# IonValveCtrl.net
KiCad netlist of a schematic drawn in Altium Designer
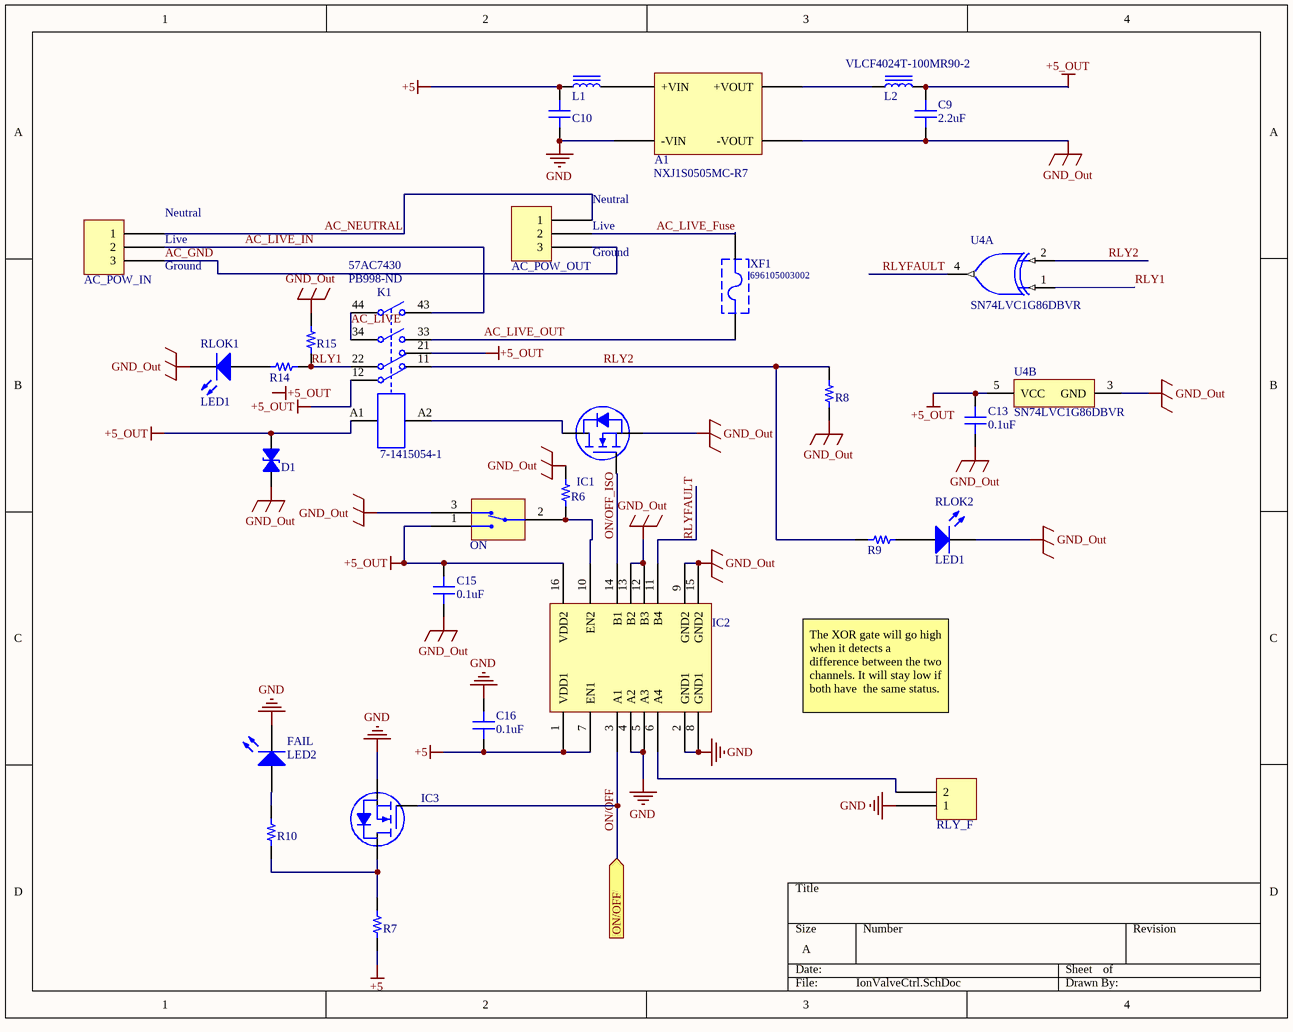
[diagram p0: IonValveCtrl.SchDoc]

(export (version "E")
  (design (tool "Eeschema 10.0.6"))
  (components
    (comp (ref "A1")
      (value "NXJ1S0505MC-R7")
      (footprint "MURATA NXJ1")
      (description "DC/DC SM 1W 5V-5V SINGLE 4.2KV")
      (fields (field (name "MANUFACTURER") "Murata Power Solutions Inc."))
      (libsource (lib "Celestial Library Database") (part "MURATA NXJ1"))
    )
    (comp (ref "AC_POW_IN")
      (value "691508110303")
      (footprint "WURTH 691508110303")
      (description "CONN TERM BLK 3POS 3.5MM BLACK")
      (fields (field (name "MANUFACTURER") "Wurth Electronics Inc") (field (name "VOLTAGE") "300V"))
      (libsource (lib "Celestial Library Database") (part "3 Pin"))
    )
    (comp (ref "AC_POW_OUT")
      (value "691508110303")
      (footprint "WURTH 691508110303")
      (description "CONN TERM BLK 3POS 3.5MM BLACK")
      (fields (field (name "MANUFACTURER") "Wurth Electronics Inc") (field (name "VOLTAGE") "300V"))
      (libsource (lib "Celestial Library Database") (part "3 Pin"))
    )
    (comp (ref "C9")
      (value "2.2uF")
      (footprint "CAP 1206/3216")
      (description "CAP CER 2.2UF 100V X7R 1206")
      (fields
        (field (name "PART NUMBER") "CL31B225KCHSNNE")
        (field (name "MANUFACTURER") "Samsung Electro-Mechanics America, Inc.")
      )
      (libsource (lib "Celestial Library Database") (part "Capacitor"))
    )
    (comp (ref "C10")
      (value "4.7uF")
      (footprint "CAP 1206/3216 - 1.8MM")
      (description "CAP CER 4.7UF 10V X7R 1206")
      (fields
        (field (name "PART NUMBER") "CL31B475KPHNNNE")
        (field (name "MANUFACTURER") "Samsung Electro-Mechanics America, Inc.")
      )
      (libsource (lib "Celestial Library Database") (part "Capacitor"))
    )
    (comp (ref "C13")
      (value "0.1uF")
      (footprint "CAP 0805/2012")
      (description "CAP CER 0.1UF 25V X7R 0805")
      (fields
        (field (name "PART NUMBER") "CL21B104KACNNNC")
        (field (name "MANUFACTURER") "Samsung Electro-Mechanics America, Inc.")
      )
      (libsource (lib "Celestial Library Database") (part "Capacitor"))
    )
    (comp (ref "C15")
      (value "0.1uF")
      (footprint "CAP 0805/2012")
      (description "CAP CER 0.1UF 25V X7R 0805")
      (fields
        (field (name "PART NUMBER") "CL21B104KACNNNC")
        (field (name "MANUFACTURER") "Samsung Electro-Mechanics America, Inc.")
      )
      (libsource (lib "Celestial Library Database") (part "Capacitor"))
    )
    (comp (ref "C16")
      (value "0.1uF")
      (footprint "CAP 0805/2012")
      (description "CAP CER 0.1UF 25V X7R 0805")
      (fields
        (field (name "PART NUMBER") "CL21B104KACNNNC")
        (field (name "MANUFACTURER") "Samsung Electro-Mechanics America, Inc.")
      )
      (libsource (lib "Celestial Library Database") (part "Capacitor"))
    )
    (comp (ref "D1")
      (value "SM15T15CA")
      (footprint "ST DO214AB SMC")
      (description "TVS DIODE 12.8VWM 27.2VC SMC")
      (fields (field (name "MANUFACTURER") "STMicroelectronics"))
      (libsource (lib "Celestial Library Database") (part "Diode Zener Bidirectional"))
    )
    (comp (ref "FAIL")
      (value "LED2")
      (footprint "LED-1")
      (description "Typical RED GaAs LED")
      (fields (field (name "PUBLISHER") "Altium Limited"))
      (libsource (lib "Miscellaneous Devices") (part "LED1"))
    )
    (comp (ref "IC1")
      (value "BSS138WH6327XTSA1")
      (footprint "INFINEON SOT-323-3")
      (description "MOSFET N-CH 60V 280MA SOT-323")
      (fields (field (name "MANUFACTURER") "Infineon Technologies"))
      (libsource (lib "Celestial Library Database") (part "INFINEON MOSFET N-CH SOT-23-3"))
    )
    (comp (ref "IC2")
      (value "SI8641BB-B-IS")
      (footprint "SI LABS SOIC-16 WIDE")
      (description "DGTL ISO 2.5KV GEN PURP 16SOIC")
      (fields (field (name "MANUFACTURER") "Silicon Labs"))
      (libsource (lib "Celestial Library Database") (part "SI LABS SI8641"))
    )
    (comp (ref "IC3")
      (value "BSS138WH6327XTSA1")
      (footprint "INFINEON SOT-323-3")
      (description "MOSFET N-CH 60V 280MA SOT-323")
      (fields (field (name "MANUFACTURER") "Infineon Technologies"))
      (libsource (lib "Celestial Library Database") (part "INFINEON MOSFET N-CH SOT-23-3"))
    )
    (comp (ref "K1")
      (value "7-1415054-1")
      (footprint "TECO-3-1415055-1-10_V")
      (description "Force Guided Relay SR4 D/M, 5 V, 8 A, -25 to 70 degC, 10-Pin THD, RoHS, Box and Tube")
      (fields
        (field (name "MANUFACTURER") "TE Connectivity")
        (field (name "SUPPLIER PART NUMBER 1") "PB998-ND")
        (field (name "SUPPLIER PART NUMBER 2") "57AC7430")
      )
      (libsource (lib "Altium Content Vault") (part "RELAY-SPST-2-10"))
    )
    (comp (ref "L1")
      (value "VLCF4024T-4R7N1R4-2")
      (footprint "TDK VLCF4024-2")
      (description "FIXED IND 4.7UH 1.43A 87 MOHM")
      (fields (field (name "MANUFACTURER") "TDK Corporation") (field (name "TOLERANCE") "30%"))
      (libsource (lib "Celestial Library Database") (part "Inductor"))
    )
    (comp (ref "L2")
      (value "VLCF4024T-100MR90-2")
      (footprint "TDK VLCF4024-2")
      (description "FIXED IND 10UH 900MA 136 MOHM")
      (fields (field (name "MANUFACTURER") "TDK Corporation") (field (name "TOLERANCE") "20%"))
      (libsource (lib "Celestial Library Database") (part "Inductor"))
    )
    (comp (ref "ON")
      (value "CL-SB-12B-01T")
      (footprint "SW_CL-SB-12B-01")
      (description "SWITCH SLIDE SPDT 200MA 12V")
      (fields (field (name "MANUFACTURER") "Nidec Copal Electronics"))
      (libsource (lib "Celestial Library Database") (part "CL-SB-12B-01T"))
    )
    (comp (ref "R6")
      (value "10k")
      (footprint "RES 1206/3216")
      (description "RES SMD 10K OHM 1% 1/4W 1206")
      (fields
        (field (name "PART NUMBER") "ERJ-8ENF1002V")
        (field (name "MANUFACTURER") "Panasonic Electronic Components")
      )
      (libsource (lib "Celestial Library Database") (part "Resistor"))
    )
    (comp (ref "R7")
      (value "620")
      (footprint "RES 1206/3216")
      (description "RES SMD 620 OHM 1% 1/4W 1206")
      (fields
        (field (name "PART NUMBER") "ERJ-8ENF6200V")
        (field (name "MANUFACTURER") "Panasonic Electronic Components")
      )
      (libsource (lib "Celestial Library Database") (part "Resistor"))
    )
    (comp (ref "R8")
      (value "10k")
      (footprint "RES 1206/3216")
      (description "RES SMD 10K OHM 1% 1/4W 1206")
      (fields
        (field (name "PART NUMBER") "ERJ-8ENF1002V")
        (field (name "MANUFACTURER") "Panasonic Electronic Components")
      )
      (libsource (lib "Celestial Library Database") (part "Resistor"))
    )
    (comp (ref "R9")
      (value "620")
      (footprint "RES 1206/3216")
      (description "RES SMD 620 OHM 1% 1/4W 1206")
      (fields
        (field (name "PART NUMBER") "ERJ-8ENF6200V")
        (field (name "MANUFACTURER") "Panasonic Electronic Components")
      )
      (libsource (lib "Celestial Library Database") (part "Resistor"))
    )
    (comp (ref "R10")
      (value "620")
      (footprint "RES 1206/3216")
      (description "RES SMD 620 OHM 1% 1/4W 1206")
      (fields
        (field (name "PART NUMBER") "ERJ-8ENF6200V")
        (field (name "MANUFACTURER") "Panasonic Electronic Components")
      )
      (libsource (lib "Celestial Library Database") (part "Resistor"))
    )
    (comp (ref "R14")
      (value "620")
      (footprint "RES 1206/3216")
      (description "RES SMD 620 OHM 1% 1/4W 1206")
      (fields
        (field (name "PART NUMBER") "ERJ-8ENF6200V")
        (field (name "MANUFACTURER") "Panasonic Electronic Components")
      )
      (libsource (lib "Celestial Library Database") (part "Resistor"))
    )
    (comp (ref "R15")
      (value "10k")
      (footprint "RES 1206/3216")
      (description "RES SMD 10K OHM 1% 1/4W 1206")
      (fields
        (field (name "PART NUMBER") "ERJ-8ENF1002V")
        (field (name "MANUFACTURER") "Panasonic Electronic Components")
      )
      (libsource (lib "Celestial Library Database") (part "Resistor"))
    )
    (comp (ref "RLOK1")
      (value "LED1")
      (footprint "LED-1")
      (description "Typical RED GaAs LED")
      (fields (field (name "PUBLISHER") "Altium Limited"))
      (libsource (lib "Miscellaneous Devices") (part "LED1"))
    )
    (comp (ref "RLOK2")
      (value "LED1")
      (footprint "LED-1")
      (description "Typical RED GaAs LED")
      (fields (field (name "PUBLISHER") "Altium Limited"))
      (libsource (lib "Miscellaneous Devices") (part "LED1"))
    )
    (comp (ref "RLY_F")
      (value "0022272021")
      (footprint "MOLEX KK 0022272021")
      (description "CONN HEADER 2POS .100 VERT TIN")
      (fields (field (name "MANUFACTURER") "Molex, LLC"))
      (libsource (lib "Celestial Library Database") (part "2 Pin"))
    )
    (comp (ref "U4")
      (value "SN74LVC1G86DBVR")
      (footprint "DBV0005A_L")
      (description "Single 2-Input Exclusive-OR Gate, DBV0005A, LARGE T&R")
      (fields
        (field (name "MANUFACTURER") "Texas Instruments")
        (field (name "GENERIC PART NUMBER") "SN74LVC1G86")
      )
      (libsource (lib "") (part "TI-XOR-1-2IN-5_1"))
    )
    (comp (ref "XF1")
      (value "696105003002")
      (footprint "696105003002")
      (description "WR-FSH Fuse Holder Blocks Fuse Holder Blocks Clip Cover for PCB")
      (fields (field (name "MANUFACTURER") "Wurth Elektronik") (field (name "PUBLISHER") "WurthElektronik"))
      (libsource (lib "Altium Content Vault") (part "WE-FUSE-2"))
    )
  )
  (nets
    (net (code "1") (name "+5") (class "Default")
      (node (ref "C10") (pin "2") (pinfunction "2_2") (pintype "passive"))
      (node (ref "C16") (pin "1") (pinfunction "1_1") (pintype "passive"))
      (node (ref "IC2") (pin "1") (pinfunction "VDD1_1") (pintype "passive"))
      (node (ref "IC2") (pin "7") (pinfunction "EN1_7") (pintype "passive"))
      (node (ref "L1") (pin "1") (pinfunction "1_1") (pintype "passive"))
      (node (ref "R7") (pin "1") (pinfunction "1_1") (pintype "passive"))
    )
    (net (code "2") (name "+5_OUT") (class "Default")
      (node (ref "C13") (pin "1") (pinfunction "1_1") (pintype "passive"))
      (node (ref "C15") (pin "1") (pinfunction "1_1") (pintype "passive"))
      (node (ref "C9") (pin "1") (pinfunction "1_1") (pintype "passive"))
      (node (ref "D1") (pin "2") (pinfunction "2_2") (pintype "passive"))
      (node (ref "IC2") (pin "16") (pinfunction "VDD2_16") (pintype "passive"))
      (node (ref "K1") (pin "12") (pinfunction "12_12") (pintype "passive"))
      (node (ref "K1") (pin "21") (pinfunction "21_21") (pintype "passive"))
      (node (ref "K1") (pin "A1") (pinfunction "A1_A1") (pintype "passive"))
      (node (ref "L2") (pin "2") (pinfunction "2_2") (pintype "passive"))
      (node (ref "ON") (pin "1") (pinfunction "GND_1") (pintype "passive"))
      (node (ref "U4") (pin "5") (pinfunction "VCC_5") (pintype "power_in"))
    )
    (net (code "3") (name "/AC_GND") (class "Default")
      (node (ref "AC_POW_IN") (pin "3") (pinfunction "3_3") (pintype "passive"))
      (node (ref "AC_POW_OUT") (pin "3") (pinfunction "3_3") (pintype "passive"))
    )
    (net (code "4") (name "/AC_LIVE") (class "Default")
      (node (ref "K1") (pin "34") (pinfunction "34_34") (pintype "passive"))
      (node (ref "K1") (pin "44") (pinfunction "44_44") (pintype "passive"))
    )
    (net (code "5") (name "/AC_LIVE_Fuse") (class "Default")
      (node (ref "AC_POW_OUT") (pin "2") (pinfunction "2_2") (pintype "passive"))
      (node (ref "XF1") (pin "2") (pinfunction "2_2") (pintype "passive"))
    )
    (net (code "6") (name "/AC_LIVE_IN") (class "Default")
      (node (ref "AC_POW_IN") (pin "2") (pinfunction "2_2") (pintype "passive"))
      (node (ref "K1") (pin "43") (pinfunction "43_43") (pintype "passive"))
    )
    (net (code "7") (name "/AC_LIVE_OUT") (class "Default")
      (node (ref "K1") (pin "33") (pinfunction "33_33") (pintype "passive"))
      (node (ref "XF1") (pin "1") (pinfunction "1_1") (pintype "passive"))
    )
    (net (code "8") (name "/AC_NEUTRAL") (class "Default")
      (node (ref "AC_POW_IN") (pin "1") (pinfunction "1_1") (pintype "passive"))
      (node (ref "AC_POW_OUT") (pin "1") (pinfunction "1_1") (pintype "passive"))
    )
    (net (code "9") (name "/ON{slash}OFF") (class "Default")
      (node (ref "IC2") (pin "3") (pinfunction "A1_3") (pintype "passive"))
      (node (ref "IC3") (pin "1") (pinfunction "G_1") (pintype "passive"))
    )
    (net (code "10") (name "/ON{slash}OFF_ISO") (class "Default")
      (node (ref "IC1") (pin "1") (pinfunction "G_1") (pintype "passive"))
      (node (ref "IC2") (pin "14") (pinfunction "B1_14") (pintype "passive"))
    )
    (net (code "11") (name "/RLY1") (class "Default")
      (node (ref "K1") (pin "22") (pinfunction "22_22") (pintype "passive"))
      (node (ref "R14") (pin "2") (pinfunction "2_2") (pintype "passive"))
      (node (ref "R15") (pin "1") (pinfunction "1_1") (pintype "passive"))
      (node (ref "U4") (pin "1") (pinfunction "A_1") (pintype "input"))
    )
    (net (code "12") (name "/RLY2") (class "Default")
      (node (ref "K1") (pin "11") (pinfunction "11_11") (pintype "passive"))
      (node (ref "R8") (pin "1") (pinfunction "1_1") (pintype "passive"))
      (node (ref "R9") (pin "1") (pinfunction "1_1") (pintype "passive"))
      (node (ref "U4") (pin "2") (pinfunction "B_2") (pintype "input"))
    )
    (net (code "13") (name "/RLYFAULT") (class "Default")
      (node (ref "IC2") (pin "11") (pinfunction "B4_11") (pintype "passive"))
      (node (ref "U4") (pin "4") (pinfunction "Y_4") (pintype "output"))
    )
    (net (code "14") (name "GND") (class "Default")
      (node (ref "A1") (pin "1") (pinfunction "-VIN_1") (pintype "passive"))
      (node (ref "C10") (pin "1") (pinfunction "1_1") (pintype "passive"))
      (node (ref "C16") (pin "2") (pinfunction "2_2") (pintype "passive"))
      (node (ref "FAIL") (pin "2") (pinfunction "K_2") (pintype "passive"))
      (node (ref "IC2") (pin "2") (pinfunction "GND1_2") (pintype "passive"))
      (node (ref "IC2") (pin "4") (pinfunction "A2_4") (pintype "passive"))
      (node (ref "IC2") (pin "5") (pinfunction "A3_5") (pintype "passive"))
      (node (ref "IC2") (pin "8") (pinfunction "GND1_8") (pintype "passive"))
      (node (ref "IC3") (pin "3") (pinfunction "S_3") (pintype "passive"))
      (node (ref "RLY_F") (pin "1") (pinfunction "1_1") (pintype "passive"))
    )
    (net (code "15") (name "GND_Out") (class "Default")
      (node (ref "A1") (pin "7") (pinfunction "-VOUT_7") (pintype "passive"))
      (node (ref "C13") (pin "2") (pinfunction "2_2") (pintype "passive"))
      (node (ref "C15") (pin "2") (pinfunction "2_2") (pintype "passive"))
      (node (ref "C9") (pin "2") (pinfunction "2_2") (pintype "passive"))
      (node (ref "D1") (pin "1") (pinfunction "1_1") (pintype "passive"))
      (node (ref "IC1") (pin "3") (pinfunction "S_3") (pintype "passive"))
      (node (ref "IC2") (pin "12") (pinfunction "B3_12") (pintype "passive"))
      (node (ref "IC2") (pin "13") (pinfunction "B2_13") (pintype "passive"))
      (node (ref "IC2") (pin "15") (pinfunction "GND2_15") (pintype "passive"))
      (node (ref "IC2") (pin "9") (pinfunction "GND2_9") (pintype "passive"))
      (node (ref "ON") (pin "3") (pinfunction "GND_3") (pintype "passive"))
      (node (ref "R15") (pin "2") (pinfunction "2_2") (pintype "passive"))
      (node (ref "R6") (pin "1") (pinfunction "1_1") (pintype "passive"))
      (node (ref "R8") (pin "2") (pinfunction "2_2") (pintype "passive"))
      (node (ref "RLOK1") (pin "2") (pinfunction "K_2") (pintype "passive"))
      (node (ref "RLOK2") (pin "2") (pinfunction "K_2") (pintype "passive"))
      (node (ref "U4") (pin "3") (pinfunction "GND_3") (pintype "power_in"))
    )
    (net (code "16") (name "Net-(A1-+VIN)") (class "Default")
      (node (ref "A1") (pin "3") (pinfunction "+VIN_3") (pintype "passive"))
      (node (ref "L1") (pin "2") (pinfunction "2_2") (pintype "passive"))
    )
    (net (code "17") (name "Net-(A1-+VOUT)") (class "Default")
      (node (ref "A1") (pin "8") (pinfunction "+VOUT_8") (pintype "passive"))
      (node (ref "L2") (pin "1") (pinfunction "1_1") (pintype "passive"))
    )
    (net (code "18") (name "Net-(FAIL-A)") (class "Default")
      (node (ref "FAIL") (pin "1") (pinfunction "A_1") (pintype "passive"))
      (node (ref "R10") (pin "2") (pinfunction "2_2") (pintype "passive"))
    )
    (net (code "19") (name "Net-(IC1-D)") (class "Default")
      (node (ref "IC1") (pin "2") (pinfunction "D_2") (pintype "passive"))
      (node (ref "K1") (pin "A2") (pinfunction "A2_A2") (pintype "passive"))
    )
    (net (code "20") (name "Net-(IC2-A4)") (class "Default")
      (node (ref "IC2") (pin "6") (pinfunction "A4_6") (pintype "passive"))
      (node (ref "RLY_F") (pin "2") (pinfunction "2_2") (pintype "passive"))
    )
    (net (code "21") (name "Net-(IC2-EN2)") (class "Default")
      (node (ref "IC2") (pin "10") (pinfunction "EN2_10") (pintype "passive"))
      (node (ref "ON") (pin "2") (pinfunction "GND_2") (pintype "passive"))
      (node (ref "R6") (pin "2") (pinfunction "2_2") (pintype "passive"))
    )
    (net (code "22") (name "Net-(IC3-D)") (class "Default")
      (node (ref "IC3") (pin "2") (pinfunction "D_2") (pintype "passive"))
      (node (ref "R10") (pin "1") (pinfunction "1_1") (pintype "passive"))
      (node (ref "R7") (pin "2") (pinfunction "2_2") (pintype "passive"))
    )
    (net (code "23") (name "Net-(RLOK1-A)") (class "Default")
      (node (ref "R14") (pin "1") (pinfunction "1_1") (pintype "passive"))
      (node (ref "RLOK1") (pin "1") (pinfunction "A_1") (pintype "passive"))
    )
    (net (code "24") (name "Net-(RLOK2-A)") (class "Default")
      (node (ref "R9") (pin "2") (pinfunction "2_2") (pintype "passive"))
      (node (ref "RLOK2") (pin "1") (pinfunction "A_1") (pintype "passive"))
    )
  )
)
